# faydal_y_k.net
KiCad netlist of a schematic drawn in Altium Designer
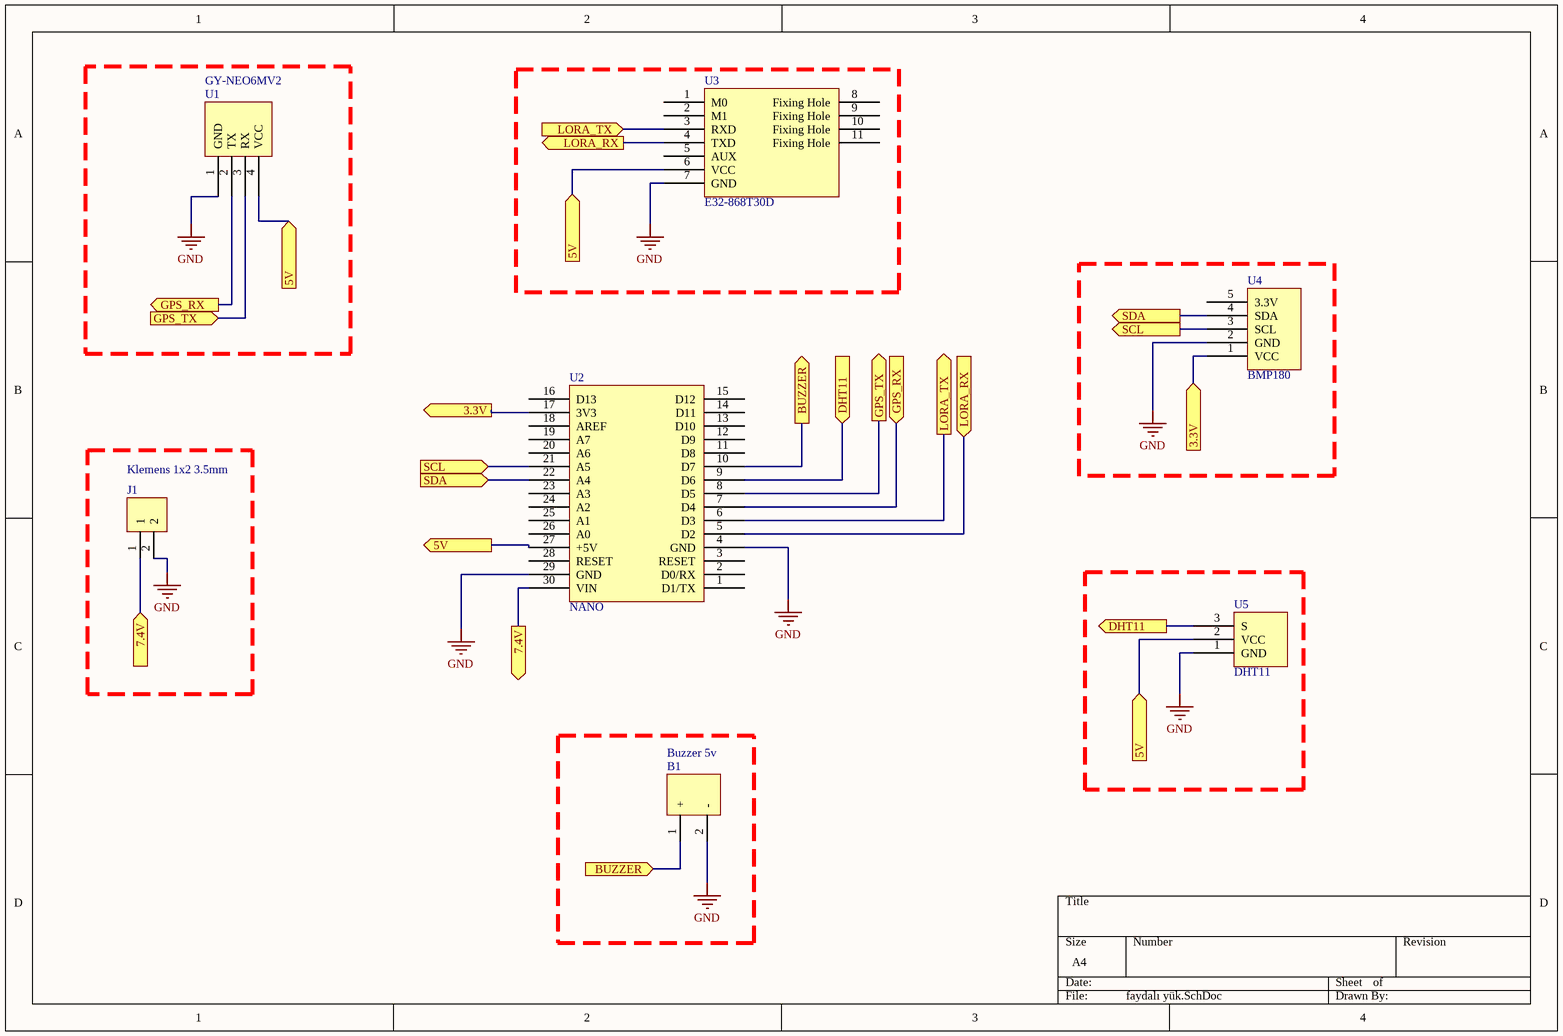
[diagram p0: faydalı yük.SchDoc]

(export (version "E")
  (design (tool "Eeschema 10.0.6"))
  (components
    (comp (ref "B1")
      (value "Buzzer 5v")
      (footprint "Buzzer 5v")
      (libsource (lib "deneme") (part "Buzzer 5v"))
    )
    (comp (ref "J1")
      (value "Klemens 1x2 3.5mm")
      (footprint "Klemens 1x2 - 3.5mm")
      (libsource (lib "deneme_yedek") (part "Klemens 1x2 3.5mm"))
    )
    (comp (ref "U1")
      (value "GY-NEO6MV2")
      (footprint "GY-NEO6MV2")
      (libsource (lib "deneme") (part "GY-NEO6MV2"))
    )
    (comp (ref "U2") (value "NANO") (footprint "nano") (libsource (lib "deneme") (part "NANO")))
    (comp (ref "U3")
      (value "E32-868T30D")
      (footprint "E32-868T30D")
      (libsource (lib "deneme") (part "E32-868T30D"))
    )
    (comp (ref "U4") (value "BMP180") (footprint "BMP180") (libsource (lib "deneme_yuk") (part "BMP180")))
    (comp (ref "U5") (value "DHT11") (footprint "DHT11") (libsource (lib "deneme_yuk") (part "DHT11")))
  )
  (nets
    (net (code "1") (name "/3.3V") (class "Default")
      (node (ref "U2") (pin "17") (pinfunction "3V3_17") (pintype "passive"))
      (node (ref "U4") (pin "1") (pinfunction "VCC_1") (pintype "passive"))
    )
    (net (code "2") (name "/5V") (class "Default")
      (node (ref "U1") (pin "4") (pinfunction "VCC_4") (pintype "passive"))
      (node (ref "U2") (pin "27") (pinfunction "+5V_27") (pintype "passive"))
      (node (ref "U3") (pin "6") (pinfunction "VCC_6") (pintype "passive"))
      (node (ref "U5") (pin "2") (pinfunction "VCC_2") (pintype "passive"))
    )
    (net (code "3") (name "/7.4V") (class "Default")
      (node (ref "J1") (pin "1") (pinfunction "1_1") (pintype "passive"))
      (node (ref "U2") (pin "30") (pinfunction "VIN_30") (pintype "passive"))
    )
    (net (code "4") (name "/BUZZER") (class "Default")
      (node (ref "B1") (pin "1") (pinfunction "+_1") (pintype "passive"))
      (node (ref "U2") (pin "10") (pinfunction "D7_10") (pintype "passive"))
    )
    (net (code "5") (name "/DHT11") (class "Default")
      (node (ref "U2") (pin "9") (pinfunction "D6_9") (pintype "passive"))
      (node (ref "U5") (pin "3") (pinfunction "S_3") (pintype "passive"))
    )
    (net (code "6") (name "/GPS_RX") (class "Default")
      (node (ref "U1") (pin "2") (pinfunction "TX_2") (pintype "passive"))
      (node (ref "U2") (pin "7") (pinfunction "D4_7") (pintype "passive"))
    )
    (net (code "7") (name "/GPS_TX") (class "Default")
      (node (ref "U1") (pin "3") (pinfunction "RX_3") (pintype "passive"))
      (node (ref "U2") (pin "8") (pinfunction "D5_8") (pintype "passive"))
    )
    (net (code "8") (name "/LORA_RX") (class "Default")
      (node (ref "U2") (pin "5") (pinfunction "D2_5") (pintype "passive"))
      (node (ref "U3") (pin "4") (pinfunction "TXD_4") (pintype "passive"))
    )
    (net (code "9") (name "/LORA_TX") (class "Default")
      (node (ref "U2") (pin "6") (pinfunction "D3_6") (pintype "passive"))
      (node (ref "U3") (pin "3") (pinfunction "RXD_3") (pintype "passive"))
    )
    (net (code "10") (name "/SCL") (class "Default")
      (node (ref "U2") (pin "21") (pinfunction "A5_21") (pintype "passive"))
      (node (ref "U4") (pin "3") (pinfunction "SCL_3") (pintype "passive"))
    )
    (net (code "11") (name "/SDA") (class "Default")
      (node (ref "U2") (pin "22") (pinfunction "A4_22") (pintype "passive"))
      (node (ref "U4") (pin "4") (pinfunction "SDA_4") (pintype "passive"))
    )
    (net (code "12") (name "GND") (class "Default")
      (node (ref "B1") (pin "2") (pinfunction "-_2") (pintype "passive"))
      (node (ref "J1") (pin "2") (pinfunction "2_2") (pintype "passive"))
      (node (ref "U1") (pin "1") (pinfunction "GND_1") (pintype "passive"))
      (node (ref "U2") (pin "29") (pinfunction "GND_29") (pintype "passive"))
      (node (ref "U2") (pin "4") (pinfunction "GND_4") (pintype "passive"))
      (node (ref "U3") (pin "7") (pinfunction "GND_7") (pintype "passive"))
      (node (ref "U4") (pin "2") (pinfunction "GND_2") (pintype "passive"))
      (node (ref "U5") (pin "1") (pinfunction "GND_1") (pintype "passive"))
    )
    (net (code "13") (name "unconnected-(U2-A0-Pad26)") (class "Default")
      (node (ref "U2") (pin "26") (pinfunction "A0_26") (pintype "passive"))
    )
    (net (code "14") (name "unconnected-(U2-A1-Pad25)") (class "Default")
      (node (ref "U2") (pin "25") (pinfunction "A1_25") (pintype "passive"))
    )
    (net (code "15") (name "unconnected-(U2-A2-Pad24)") (class "Default")
      (node (ref "U2") (pin "24") (pinfunction "A2_24") (pintype "passive"))
    )
    (net (code "16") (name "unconnected-(U2-A3-Pad23)") (class "Default")
      (node (ref "U2") (pin "23") (pinfunction "A3_23") (pintype "passive"))
    )
    (net (code "17") (name "unconnected-(U2-A6-Pad20)") (class "Default")
      (node (ref "U2") (pin "20") (pinfunction "A6_20") (pintype "passive"))
    )
    (net (code "18") (name "unconnected-(U2-A7-Pad19)") (class "Default")
      (node (ref "U2") (pin "19") (pinfunction "A7_19") (pintype "passive"))
    )
    (net (code "19") (name "unconnected-(U2-AREF-Pad18)") (class "Default")
      (node (ref "U2") (pin "18") (pinfunction "AREF_18") (pintype "passive"))
    )
    (net (code "20") (name "unconnected-(U2-D0{slash}RX-Pad2)") (class "Default")
      (node (ref "U2") (pin "2") (pinfunction "D0/RX_2") (pintype "passive"))
    )
    (net (code "21") (name "unconnected-(U2-D1{slash}TX-Pad1)") (class "Default")
      (node (ref "U2") (pin "1") (pinfunction "D1/TX_1") (pintype "passive"))
    )
    (net (code "22") (name "unconnected-(U2-D8-Pad11)") (class "Default")
      (node (ref "U2") (pin "11") (pinfunction "D8_11") (pintype "passive"))
    )
    (net (code "23") (name "unconnected-(U2-D9-Pad12)") (class "Default")
      (node (ref "U2") (pin "12") (pinfunction "D9_12") (pintype "passive"))
    )
    (net (code "24") (name "unconnected-(U2-D10-Pad13)") (class "Default")
      (node (ref "U2") (pin "13") (pinfunction "D10_13") (pintype "passive"))
    )
    (net (code "25") (name "unconnected-(U2-D11-Pad14)") (class "Default")
      (node (ref "U2") (pin "14") (pinfunction "D11_14") (pintype "passive"))
    )
    (net (code "26") (name "unconnected-(U2-D12-Pad15)") (class "Default")
      (node (ref "U2") (pin "15") (pinfunction "D12_15") (pintype "passive"))
    )
    (net (code "27") (name "unconnected-(U2-D13-Pad16)") (class "Default")
      (node (ref "U2") (pin "16") (pinfunction "D13_16") (pintype "passive"))
    )
    (net (code "28") (name "unconnected-(U2-RESET-Pad3)") (class "Default")
      (node (ref "U2") (pin "3") (pinfunction "RESET_3") (pintype "passive"))
    )
    (net (code "29") (name "unconnected-(U2-RESET-Pad28)") (class "Default")
      (node (ref "U2") (pin "28") (pinfunction "RESET_28") (pintype "passive"))
    )
    (net (code "30") (name "unconnected-(U3-AUX-Pad5)") (class "Default")
      (node (ref "U3") (pin "5") (pinfunction "AUX_5") (pintype "passive"))
    )
    (net (code "31") (name "unconnected-(U3-Fixing_Hole-Pad8)") (class "Default")
      (node (ref "U3") (pin "8") (pinfunction "Fixing_Hole_8") (pintype "passive"))
    )
    (net (code "32") (name "unconnected-(U3-Fixing_Hole-Pad9)") (class "Default")
      (node (ref "U3") (pin "9") (pinfunction "Fixing_Hole_9") (pintype "passive"))
    )
    (net (code "33") (name "unconnected-(U3-Fixing_Hole-Pad10)") (class "Default")
      (node (ref "U3") (pin "10") (pinfunction "Fixing_Hole_10") (pintype "passive"))
    )
    (net (code "34") (name "unconnected-(U3-Fixing_Hole-Pad11)") (class "Default")
      (node (ref "U3") (pin "11") (pinfunction "Fixing_Hole_11") (pintype "passive"))
    )
    (net (code "35") (name "unconnected-(U3-M0-Pad1)") (class "Default")
      (node (ref "U3") (pin "1") (pinfunction "M0_1") (pintype "passive"))
    )
    (net (code "36") (name "unconnected-(U3-M1-Pad2)") (class "Default")
      (node (ref "U3") (pin "2") (pinfunction "M1_2") (pintype "passive"))
    )
    (net (code "37") (name "unconnected-(U4-3.3V-Pad5)") (class "Default")
      (node (ref "U4") (pin "5") (pinfunction "3.3V_5") (pintype "passive"))
    )
  )
)
